# REMO_4OUT.net
KiCad netlist of a schematic drawn in Altium Designer
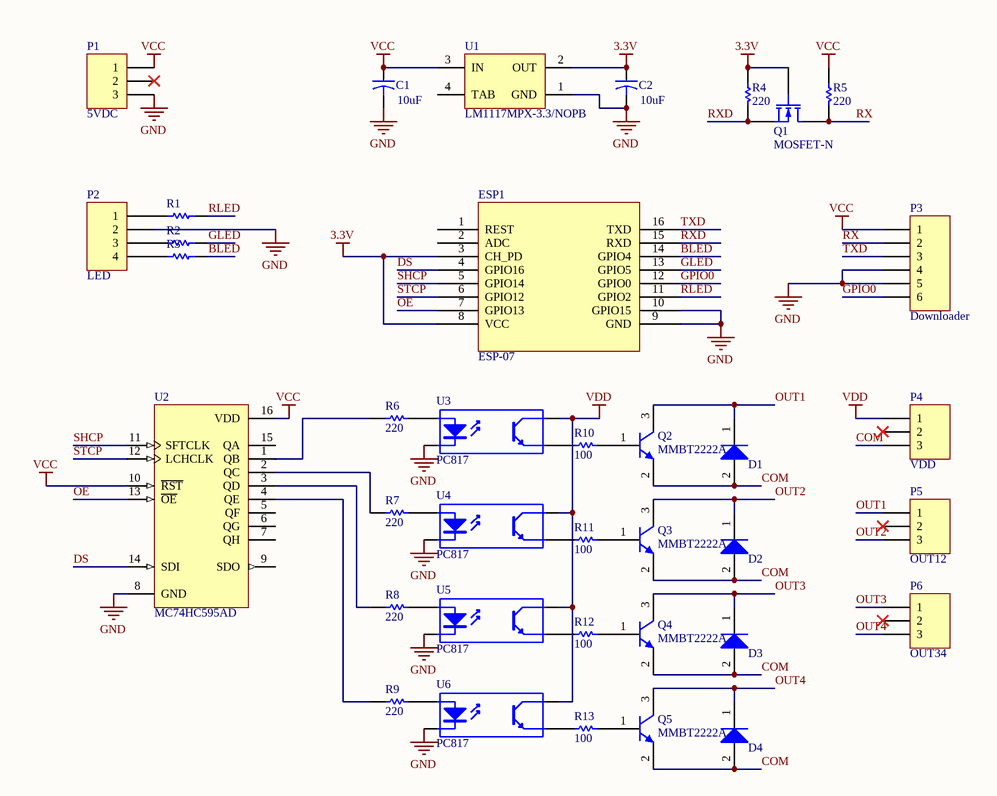
[diagram p0: REMO_4OUT.SchDoc]

(export (version "E")
  (design (tool "Eeschema 10.0.6"))
  (components
    (comp (ref "C1")
      (value "10uF")
      (footprint "6-0805_L")
      (description "Capacitor")
      (fields (field (name "Comment") "Cap2") (field (name "PUBLISHER") "Altium Limited"))
      (libsource (lib "Miscellaneous Devices") (part "Cap2"))
    )
    (comp (ref "C2")
      (value "10uF")
      (footprint "6-0805_L")
      (description "Capacitor")
      (fields (field (name "Comment") "Cap2") (field (name "PUBLISHER") "Altium Limited"))
      (libsource (lib "Miscellaneous Devices") (part "Cap2"))
    )
    (comp (ref "D1")
      (value "MMSD4148T3G")
      (footprint "ONSC-SOD-123-2-425-04_V")
      (description "Switching Diode, 2-Pin SOD-123, Pb-Free, Tape and Reel")
      (fields (field (name "MANUFACTURER") "On Semiconductor"))
      (libsource (lib "ON Semi Small Signal Switching Diodes") (part "MMSD4148T3G"))
    )
    (comp (ref "D2")
      (value "MMSD4148T3G")
      (footprint "ONSC-SOD-123-2-425-04_V")
      (description "Switching Diode, 2-Pin SOD-123, Pb-Free, Tape and Reel")
      (fields (field (name "MANUFACTURER") "On Semiconductor"))
      (libsource (lib "ON Semi Small Signal Switching Diodes") (part "MMSD4148T3G"))
    )
    (comp (ref "D3")
      (value "MMSD4148T3G")
      (footprint "ONSC-SOD-123-2-425-04_V")
      (description "Switching Diode, 2-Pin SOD-123, Pb-Free, Tape and Reel")
      (fields (field (name "MANUFACTURER") "On Semiconductor"))
      (libsource (lib "ON Semi Small Signal Switching Diodes") (part "MMSD4148T3G"))
    )
    (comp (ref "D4")
      (value "MMSD4148T3G")
      (footprint "ONSC-SOD-123-2-425-04_V")
      (description "Switching Diode, 2-Pin SOD-123, Pb-Free, Tape and Reel")
      (fields (field (name "MANUFACTURER") "On Semiconductor"))
      (libsource (lib "ON Semi Small Signal Switching Diodes") (part "MMSD4148T3G"))
    )
    (comp (ref "ESP1")
      (value "ESP-07")
      (footprint "ESP-07")
      (libsource (lib "ModegiLibrary") (part "ESP-07"))
    )
    (comp (ref "P1")
      (value "5VDC")
      (footprint "HDR1X3")
      (description "Header, 3-Pin")
      (fields (field (name "PUBLISHER") "Altium Limited"))
      (libsource (lib "Miscellaneous Connectors") (part "Header 3"))
    )
    (comp (ref "P2")
      (value "LED")
      (footprint "HDR1X4")
      (description "Header, 4-Pin")
      (fields (field (name "PUBLISHER") "Altium Limited"))
      (libsource (lib "Miscellaneous Connectors") (part "Header 4"))
    )
    (comp (ref "P3")
      (value "Downloader")
      (footprint "HDR1X6")
      (description "Header, 6-Pin")
      (fields (field (name "PUBLISHER") "Altium Limited"))
      (libsource (lib "Miscellaneous Connectors") (part "Header 6"))
    )
    (comp (ref "P4")
      (value "VDD")
      (footprint "HDR1X3")
      (description "Header, 3-Pin")
      (fields (field (name "PUBLISHER") "Altium Limited"))
      (libsource (lib "") (part "Header 3_1"))
    )
    (comp (ref "P5")
      (value "OUT12")
      (footprint "HDR1X3")
      (description "Header, 3-Pin")
      (fields (field (name "PUBLISHER") "Altium Limited"))
      (libsource (lib "") (part "Header 3_1"))
    )
    (comp (ref "P6")
      (value "OUT34")
      (footprint "HDR1X3")
      (description "Header, 3-Pin")
      (fields (field (name "PUBLISHER") "Altium Limited"))
      (libsource (lib "") (part "Header 3_1"))
    )
    (comp (ref "Q1")
      (value "MOSFET-N")
      (footprint "SOT23_N")
      (description "N-Channel MOSFET")
      (fields (field (name "PUBLISHER") "Altium Limited"))
      (libsource (lib "Miscellaneous Devices") (part "MOSFET-N"))
    )
    (comp (ref "Q2")
      (value "MMBT2222A")
      (footprint "INF-SOT23_N")
      (description "NPN Silicon Switching Transistor, 40 V VCEO, 600 mA IC, SOT23, Reel, Green")
      (fields (field (name "MANUFACTURER") "Infineon"))
      (libsource (lib "Infineon_Transistor_&_Diode") (part "MMBT2222A"))
    )
    (comp (ref "Q3")
      (value "MMBT2222A")
      (footprint "INF-SOT23_N")
      (description "NPN Silicon Switching Transistor, 40 V VCEO, 600 mA IC, SOT23, Reel, Green")
      (fields (field (name "MANUFACTURER") "Infineon"))
      (libsource (lib "Infineon_Transistor_&_Diode") (part "MMBT2222A"))
    )
    (comp (ref "Q4")
      (value "MMBT2222A")
      (footprint "INF-SOT23_N")
      (description "NPN Silicon Switching Transistor, 40 V VCEO, 600 mA IC, SOT23, Reel, Green")
      (fields (field (name "MANUFACTURER") "Infineon"))
      (libsource (lib "Infineon_Transistor_&_Diode") (part "MMBT2222A"))
    )
    (comp (ref "Q5")
      (value "MMBT2222A")
      (footprint "INF-SOT23_N")
      (description "NPN Silicon Switching Transistor, 40 V VCEO, 600 mA IC, SOT23, Reel, Green")
      (fields (field (name "MANUFACTURER") "Infineon"))
      (libsource (lib "Infineon_Transistor_&_Diode") (part "MMBT2222A"))
    )
    (comp (ref "R1")
      (value "Res1")
      (footprint "AXIAL-0.3")
      (description "Resistor")
      (fields (field (name "PUBLISHER") "Altium Limited"))
      (libsource (lib "Miscellaneous Devices") (part "Res1"))
    )
    (comp (ref "R2")
      (value "Res1")
      (footprint "AXIAL-0.3")
      (description "Resistor")
      (fields (field (name "PUBLISHER") "Altium Limited"))
      (libsource (lib "Miscellaneous Devices") (part "Res1"))
    )
    (comp (ref "R3")
      (value "Res1")
      (footprint "AXIAL-0.3")
      (description "Resistor")
      (fields (field (name "PUBLISHER") "Altium Limited"))
      (libsource (lib "Miscellaneous Devices") (part "Res1"))
    )
    (comp (ref "R4")
      (value "220")
      (footprint "6-0805_N")
      (description "RES0805")
      (libsource (lib "ModegiLibrary") (part "RES0805"))
    )
    (comp (ref "R5")
      (value "220")
      (footprint "6-0805_N")
      (description "RES0805")
      (libsource (lib "ModegiLibrary") (part "RES0805"))
    )
    (comp (ref "R6")
      (value "220")
      (footprint "6-0805_N")
      (description "RES0805")
      (libsource (lib "ModegiLibrary") (part "RES0805"))
    )
    (comp (ref "R7")
      (value "220")
      (footprint "6-0805_N")
      (description "RES0805")
      (libsource (lib "ModegiLibrary") (part "RES0805"))
    )
    (comp (ref "R8")
      (value "220")
      (footprint "6-0805_N")
      (description "RES0805")
      (libsource (lib "ModegiLibrary") (part "RES0805"))
    )
    (comp (ref "R9")
      (value "220")
      (footprint "6-0805_N")
      (description "RES0805")
      (libsource (lib "ModegiLibrary") (part "RES0805"))
    )
    (comp (ref "R10")
      (value "100")
      (footprint "6-0805_N")
      (description "RES0805")
      (libsource (lib "ModegiLibrary") (part "RES0805"))
    )
    (comp (ref "R11")
      (value "100")
      (footprint "6-0805_N")
      (description "RES0805")
      (libsource (lib "ModegiLibrary") (part "RES0805"))
    )
    (comp (ref "R12")
      (value "100")
      (footprint "6-0805_N")
      (description "RES0805")
      (libsource (lib "ModegiLibrary") (part "RES0805"))
    )
    (comp (ref "R13")
      (value "100")
      (footprint "6-0805_N")
      (description "RES0805")
      (libsource (lib "ModegiLibrary") (part "RES0805"))
    )
    (comp (ref "U1")
      (value "LM1117MPX-3.3/NOPB")
      (footprint "MP04A_N")
      (description "800mA Low-Dropout Linear Regulator, 4-pin SOT-223, Pb-Free")
      (fields (field (name "MANUFACTURER") "National Semiconductor"))
      (libsource (lib "National Semiconductor LDO") (part "LM1117MPX-3.3/NOPB"))
    )
    (comp (ref "U2")
      (value "MC74HC595AD")
      (footprint "751B-05_N")
      (description "8-Bit Serial-Input/Serial or Prallel-Output Shift Register with Latched 3-State Outputs")
      (fields (field (name "PUBLISHER") "Altium Limited"))
      (libsource (lib "ON Semi Logic Register") (part "MC74HC595AD"))
    )
    (comp (ref "U3")
      (value "PC817")
      (footprint "DIP-4")
      (description "4-Pin Phototransistor Optocoupler")
      (fields (field (name "PUBLISHER") "Altium Limited"))
      (libsource (lib "Miscellaneous Devices") (part "Optoisolator1"))
    )
    (comp (ref "U4")
      (value "PC817")
      (footprint "DIP-4")
      (description "4-Pin Phototransistor Optocoupler")
      (fields (field (name "PUBLISHER") "Altium Limited"))
      (libsource (lib "Miscellaneous Devices") (part "Optoisolator1"))
    )
    (comp (ref "U5")
      (value "PC817")
      (footprint "DIP-4")
      (description "4-Pin Phototransistor Optocoupler")
      (fields (field (name "PUBLISHER") "Altium Limited"))
      (libsource (lib "Miscellaneous Devices") (part "Optoisolator1"))
    )
    (comp (ref "U6")
      (value "PC817")
      (footprint "DIP-4")
      (description "4-Pin Phototransistor Optocoupler")
      (fields (field (name "PUBLISHER") "Altium Limited"))
      (libsource (lib "Miscellaneous Devices") (part "Optoisolator1"))
    )
  )
  (nets
    (net (code "1") (name "/BLED") (class "Default")
      (node (ref "ESP1") (pin "14") (pinfunction "GPIO4_14") (pintype "passive"))
      (node (ref "R3") (pin "2") (pinfunction "2_2") (pintype "passive"))
    )
    (net (code "2") (name "/COM") (class "Default")
      (node (ref "D1") (pin "2") (pinfunction "A_2") (pintype "passive"))
      (node (ref "D2") (pin "2") (pinfunction "A_2") (pintype "passive"))
      (node (ref "D3") (pin "2") (pinfunction "A_2") (pintype "passive"))
      (node (ref "D4") (pin "2") (pinfunction "A_2") (pintype "passive"))
      (node (ref "P4") (pin "3") (pinfunction "3_3") (pintype "passive"))
      (node (ref "Q2") (pin "2") (pinfunction "E_2") (pintype "passive"))
      (node (ref "Q3") (pin "2") (pinfunction "E_2") (pintype "passive"))
      (node (ref "Q4") (pin "2") (pinfunction "E_2") (pintype "passive"))
      (node (ref "Q5") (pin "2") (pinfunction "E_2") (pintype "passive"))
    )
    (net (code "3") (name "/DS") (class "Default")
      (node (ref "ESP1") (pin "4") (pinfunction "GPIO16_4") (pintype "passive"))
      (node (ref "U2") (pin "14") (pinfunction "SDI_14") (pintype "input"))
    )
    (net (code "4") (name "/GLED") (class "Default")
      (node (ref "ESP1") (pin "13") (pinfunction "GPIO5_13") (pintype "passive"))
      (node (ref "R2") (pin "2") (pinfunction "2_2") (pintype "passive"))
    )
    (net (code "5") (name "/GPIO0") (class "Default")
      (node (ref "ESP1") (pin "12") (pinfunction "GPIO0_12") (pintype "passive"))
      (node (ref "P3") (pin "6") (pinfunction "6_6") (pintype "passive"))
    )
    (net (code "6") (name "/OE") (class "Default")
      (node (ref "ESP1") (pin "7") (pinfunction "GPIO13_7") (pintype "passive"))
      (node (ref "U2") (pin "13") (pinfunction "~{OE}_13") (pintype "input"))
    )
    (net (code "7") (name "/OUT1") (class "Default")
      (node (ref "D1") (pin "1") (pinfunction "K_1") (pintype "passive"))
      (node (ref "P5") (pin "1") (pinfunction "1_1") (pintype "passive"))
      (node (ref "Q2") (pin "3") (pinfunction "C_3") (pintype "passive"))
    )
    (net (code "8") (name "/OUT2") (class "Default")
      (node (ref "D2") (pin "1") (pinfunction "K_1") (pintype "passive"))
      (node (ref "P5") (pin "3") (pinfunction "3_3") (pintype "passive"))
      (node (ref "Q3") (pin "3") (pinfunction "C_3") (pintype "passive"))
    )
    (net (code "9") (name "/OUT3") (class "Default")
      (node (ref "D3") (pin "1") (pinfunction "K_1") (pintype "passive"))
      (node (ref "P6") (pin "1") (pinfunction "1_1") (pintype "passive"))
      (node (ref "Q4") (pin "3") (pinfunction "C_3") (pintype "passive"))
    )
    (net (code "10") (name "/OUT4") (class "Default")
      (node (ref "D4") (pin "1") (pinfunction "K_1") (pintype "passive"))
      (node (ref "P6") (pin "3") (pinfunction "3_3") (pintype "passive"))
      (node (ref "Q5") (pin "3") (pinfunction "C_3") (pintype "passive"))
    )
    (net (code "11") (name "/RLED") (class "Default")
      (node (ref "ESP1") (pin "11") (pinfunction "GPIO2_11") (pintype "passive"))
      (node (ref "R1") (pin "2") (pinfunction "2_2") (pintype "passive"))
    )
    (net (code "12") (name "/RX") (class "Default")
      (node (ref "P3") (pin "2") (pinfunction "2_2") (pintype "passive"))
      (node (ref "Q1") (pin "1") (pinfunction "D_1") (pintype "passive"))
      (node (ref "R5") (pin "2") (pinfunction "2_2") (pintype "passive"))
    )
    (net (code "13") (name "/RXD") (class "Default")
      (node (ref "ESP1") (pin "15") (pinfunction "RXD_15") (pintype "passive"))
      (node (ref "Q1") (pin "3") (pinfunction "S_3") (pintype "passive"))
      (node (ref "R4") (pin "2") (pinfunction "2_2") (pintype "passive"))
    )
    (net (code "14") (name "/SHCP") (class "Default")
      (node (ref "ESP1") (pin "5") (pinfunction "GPIO14_5") (pintype "passive"))
      (node (ref "U2") (pin "11") (pinfunction "SFTCLK_11") (pintype "input"))
    )
    (net (code "15") (name "/STCP") (class "Default")
      (node (ref "ESP1") (pin "6") (pinfunction "GPIO12_6") (pintype "passive"))
      (node (ref "U2") (pin "12") (pinfunction "LCHCLK_12") (pintype "input"))
    )
    (net (code "16") (name "/TXD") (class "Default")
      (node (ref "ESP1") (pin "16") (pinfunction "TXD_16") (pintype "passive"))
      (node (ref "P3") (pin "3") (pinfunction "3_3") (pintype "passive"))
    )
    (net (code "17") (name "3.3V") (class "Default")
      (node (ref "C2") (pin "1") (pinfunction "1_1") (pintype "passive"))
      (node (ref "ESP1") (pin "3") (pinfunction "CH_PD_3") (pintype "passive"))
      (node (ref "ESP1") (pin "8") (pinfunction "VCC_8") (pintype "passive"))
      (node (ref "Q1") (pin "2") (pinfunction "G_2") (pintype "passive"))
      (node (ref "R4") (pin "1") (pinfunction "1_1") (pintype "passive"))
      (node (ref "U1") (pin "2") (pinfunction "OUT_2") (pintype "power_in"))
    )
    (net (code "18") (name "GND") (class "Default")
      (node (ref "C1") (pin "2") (pinfunction "2_2") (pintype "passive"))
      (node (ref "C2") (pin "2") (pinfunction "2_2") (pintype "passive"))
      (node (ref "ESP1") (pin "10") (pinfunction "GPIO15_10") (pintype "passive"))
      (node (ref "ESP1") (pin "9") (pinfunction "GND_9") (pintype "passive"))
      (node (ref "P1") (pin "3") (pinfunction "3_3") (pintype "passive"))
      (node (ref "P2") (pin "2") (pinfunction "2_2") (pintype "passive"))
      (node (ref "P3") (pin "4") (pinfunction "4_4") (pintype "passive"))
      (node (ref "P3") (pin "5") (pinfunction "5_5") (pintype "passive"))
      (node (ref "U1") (pin "1") (pinfunction "GND_1") (pintype "power_in"))
      (node (ref "U2") (pin "8") (pinfunction "GND_8") (pintype "power_in"))
      (node (ref "U3") (pin "2") (pinfunction "K_2") (pintype "passive"))
      (node (ref "U4") (pin "2") (pinfunction "K_2") (pintype "passive"))
      (node (ref "U5") (pin "2") (pinfunction "K_2") (pintype "passive"))
      (node (ref "U6") (pin "2") (pinfunction "K_2") (pintype "passive"))
    )
    (net (code "19") (name "Net-(P2-Pad1)") (class "Default")
      (node (ref "P2") (pin "1") (pinfunction "1_1") (pintype "passive"))
      (node (ref "R1") (pin "1") (pinfunction "1_1") (pintype "passive"))
    )
    (net (code "20") (name "Net-(P2-Pad3)") (class "Default")
      (node (ref "P2") (pin "3") (pinfunction "3_3") (pintype "passive"))
      (node (ref "R2") (pin "1") (pinfunction "1_1") (pintype "passive"))
    )
    (net (code "21") (name "Net-(P2-Pad4)") (class "Default")
      (node (ref "P2") (pin "4") (pinfunction "4_4") (pintype "passive"))
      (node (ref "R3") (pin "1") (pinfunction "1_1") (pintype "passive"))
    )
    (net (code "22") (name "Net-(Q2-B)") (class "Default")
      (node (ref "Q2") (pin "1") (pinfunction "B_1") (pintype "passive"))
      (node (ref "R10") (pin "2") (pinfunction "2_2") (pintype "passive"))
    )
    (net (code "23") (name "Net-(Q3-B)") (class "Default")
      (node (ref "Q3") (pin "1") (pinfunction "B_1") (pintype "passive"))
      (node (ref "R11") (pin "2") (pinfunction "2_2") (pintype "passive"))
    )
    (net (code "24") (name "Net-(Q4-B)") (class "Default")
      (node (ref "Q4") (pin "1") (pinfunction "B_1") (pintype "passive"))
      (node (ref "R12") (pin "2") (pinfunction "2_2") (pintype "passive"))
    )
    (net (code "25") (name "Net-(Q5-B)") (class "Default")
      (node (ref "Q5") (pin "1") (pinfunction "B_1") (pintype "passive"))
      (node (ref "R13") (pin "2") (pinfunction "2_2") (pintype "passive"))
    )
    (net (code "26") (name "Net-(U2-QB)") (class "Default")
      (node (ref "R6") (pin "1") (pinfunction "1_1") (pintype "passive"))
      (node (ref "U2") (pin "1") (pinfunction "QB_1") (pintype "tri_state"))
    )
    (net (code "27") (name "Net-(U2-QC)") (class "Default")
      (node (ref "R7") (pin "1") (pinfunction "1_1") (pintype "passive"))
      (node (ref "U2") (pin "2") (pinfunction "QC_2") (pintype "tri_state"))
    )
    (net (code "28") (name "Net-(U2-QD)") (class "Default")
      (node (ref "R8") (pin "1") (pinfunction "1_1") (pintype "passive"))
      (node (ref "U2") (pin "3") (pinfunction "QD_3") (pintype "tri_state"))
    )
    (net (code "29") (name "Net-(U2-QE)") (class "Default")
      (node (ref "R9") (pin "1") (pinfunction "1_1") (pintype "passive"))
      (node (ref "U2") (pin "4") (pinfunction "QE_4") (pintype "tri_state"))
    )
    (net (code "30") (name "Net-(U3-A)") (class "Default")
      (node (ref "R6") (pin "2") (pinfunction "2_2") (pintype "passive"))
      (node (ref "U3") (pin "1") (pinfunction "A_1") (pintype "passive"))
    )
    (net (code "31") (name "Net-(U3-E)") (class "Default")
      (node (ref "R10") (pin "1") (pinfunction "1_1") (pintype "passive"))
      (node (ref "U3") (pin "3") (pinfunction "E_3") (pintype "passive"))
    )
    (net (code "32") (name "Net-(U4-A)") (class "Default")
      (node (ref "R7") (pin "2") (pinfunction "2_2") (pintype "passive"))
      (node (ref "U4") (pin "1") (pinfunction "A_1") (pintype "passive"))
    )
    (net (code "33") (name "Net-(U4-E)") (class "Default")
      (node (ref "R11") (pin "1") (pinfunction "1_1") (pintype "passive"))
      (node (ref "U4") (pin "3") (pinfunction "E_3") (pintype "passive"))
    )
    (net (code "34") (name "Net-(U5-A)") (class "Default")
      (node (ref "R8") (pin "2") (pinfunction "2_2") (pintype "passive"))
      (node (ref "U5") (pin "1") (pinfunction "A_1") (pintype "passive"))
    )
    (net (code "35") (name "Net-(U5-E)") (class "Default")
      (node (ref "R12") (pin "1") (pinfunction "1_1") (pintype "passive"))
      (node (ref "U5") (pin "3") (pinfunction "E_3") (pintype "passive"))
    )
    (net (code "36") (name "Net-(U6-A)") (class "Default")
      (node (ref "R9") (pin "2") (pinfunction "2_2") (pintype "passive"))
      (node (ref "U6") (pin "1") (pinfunction "A_1") (pintype "passive"))
    )
    (net (code "37") (name "Net-(U6-E)") (class "Default")
      (node (ref "R13") (pin "1") (pinfunction "1_1") (pintype "passive"))
      (node (ref "U6") (pin "3") (pinfunction "E_3") (pintype "passive"))
    )
    (net (code "38") (name "VCC") (class "Default")
      (node (ref "C1") (pin "1") (pinfunction "1_1") (pintype "passive"))
      (node (ref "P1") (pin "1") (pinfunction "1_1") (pintype "passive"))
      (node (ref "P3") (pin "1") (pinfunction "1_1") (pintype "passive"))
      (node (ref "R5") (pin "1") (pinfunction "1_1") (pintype "passive"))
      (node (ref "U1") (pin "3") (pinfunction "IN_3") (pintype "power_in"))
      (node (ref "U2") (pin "10") (pinfunction "~{RST}_10") (pintype "input"))
      (node (ref "U2") (pin "16") (pinfunction "VDD_16") (pintype "power_in"))
    )
    (net (code "39") (name "VDD") (class "Default")
      (node (ref "P4") (pin "1") (pinfunction "1_1") (pintype "passive"))
      (node (ref "U3") (pin "4") (pinfunction "C_4") (pintype "passive"))
      (node (ref "U4") (pin "4") (pinfunction "C_4") (pintype "passive"))
      (node (ref "U5") (pin "4") (pinfunction "C_4") (pintype "passive"))
      (node (ref "U6") (pin "4") (pinfunction "C_4") (pintype "passive"))
    )
    (net (code "40") (name "unconnected-(ESP1-ADC-Pad2)") (class "Default")
      (node (ref "ESP1") (pin "2") (pinfunction "ADC_2") (pintype "passive"))
    )
    (net (code "41") (name "unconnected-(ESP1-REST-Pad1)") (class "Default")
      (node (ref "ESP1") (pin "1") (pinfunction "REST_1") (pintype "passive"))
    )
    (net (code "42") (name "unconnected-(P1-Pad2)") (class "Default")
      (node (ref "P1") (pin "2") (pinfunction "2_2") (pintype "passive+no_connect"))
    )
    (net (code "43") (name "unconnected-(P4-Pad2)") (class "Default")
      (node (ref "P4") (pin "2") (pinfunction "2_2") (pintype "passive+no_connect"))
    )
    (net (code "44") (name "unconnected-(P5-Pad2)") (class "Default")
      (node (ref "P5") (pin "2") (pinfunction "2_2") (pintype "passive+no_connect"))
    )
    (net (code "45") (name "unconnected-(P6-Pad2)") (class "Default")
      (node (ref "P6") (pin "2") (pinfunction "2_2") (pintype "passive+no_connect"))
    )
    (net (code "46") (name "unconnected-(U1-TAB-Pad4)") (class "Default")
      (node (ref "U1") (pin "4") (pinfunction "TAB_4") (pintype "power_in"))
    )
    (net (code "47") (name "unconnected-(U2-QA-Pad15)") (class "Default")
      (node (ref "U2") (pin "15") (pinfunction "QA_15") (pintype "tri_state"))
    )
    (net (code "48") (name "unconnected-(U2-QF-Pad5)") (class "Default")
      (node (ref "U2") (pin "5") (pinfunction "QF_5") (pintype "tri_state"))
    )
    (net (code "49") (name "unconnected-(U2-QG-Pad6)") (class "Default")
      (node (ref "U2") (pin "6") (pinfunction "QG_6") (pintype "tri_state"))
    )
    (net (code "50") (name "unconnected-(U2-QH-Pad7)") (class "Default")
      (node (ref "U2") (pin "7") (pinfunction "QH_7") (pintype "tri_state"))
    )
    (net (code "51") (name "unconnected-(U2-SDO-Pad9)") (class "Default")
      (node (ref "U2") (pin "9") (pinfunction "SDO_9") (pintype "output"))
    )
  )
)
